# Power_LED_1.net
KiCad netlist of a schematic drawn in Altium Designer
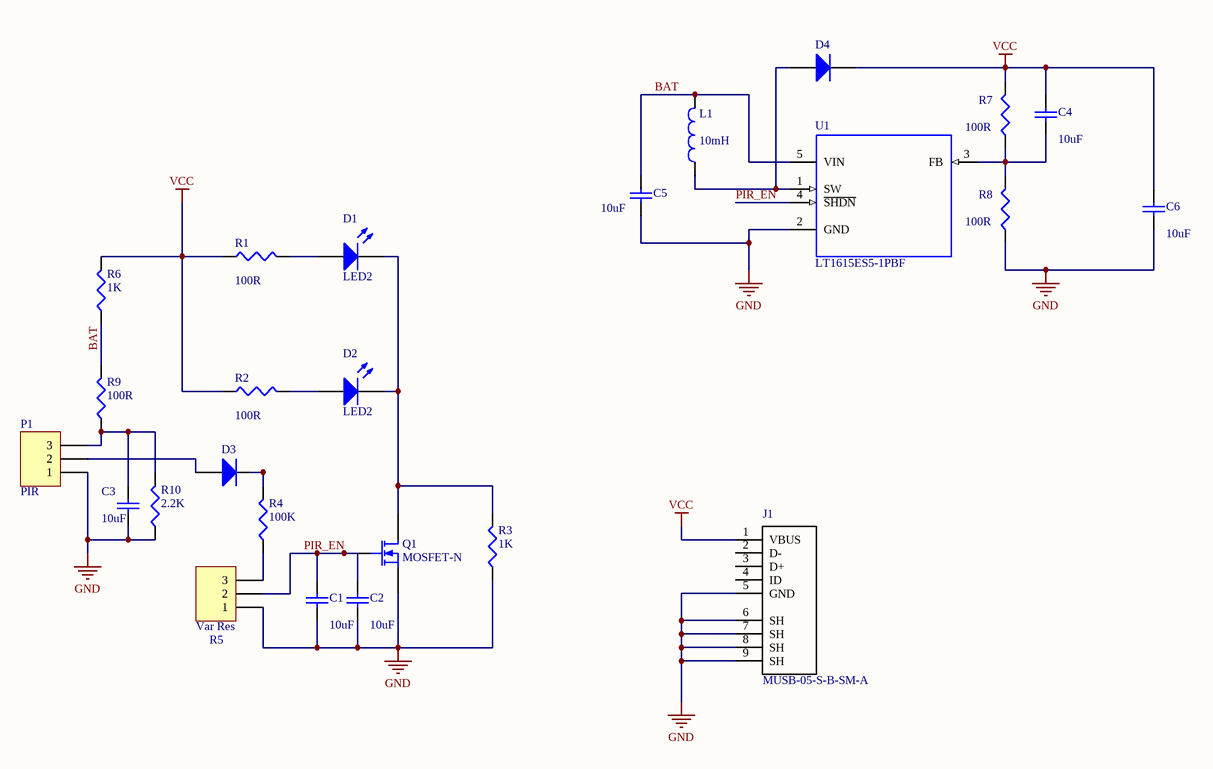
[diagram p0: Power_LED_1.SchDoc]

(export (version "E")
  (design (tool "Eeschema 10.0.6"))
  (components
    (comp (ref "C1")
      (value "10uF")
      (footprint "C1206")
      (description "Capacitor (Semiconductor SIM Model)")
      (fields (field (name "PUBLISHER") "Altium Limited"))
      (libsource (lib "Miscellaneous Devices") (part "Cap Semi"))
    )
    (comp (ref "C2")
      (value "10uF")
      (footprint "C0805")
      (description "Capacitor (Semiconductor SIM Model)")
      (fields (field (name "PUBLISHER") "Altium Limited"))
      (libsource (lib "Miscellaneous Devices") (part "Cap Semi"))
    )
    (comp (ref "C3")
      (value "10uF")
      (footprint "C1206")
      (description "Capacitor (Semiconductor SIM Model)")
      (fields (field (name "PUBLISHER") "Altium Limited"))
      (libsource (lib "Miscellaneous Devices") (part "Cap Semi"))
    )
    (comp (ref "C4")
      (value "10uF")
      (footprint "C0805")
      (description "Capacitor (Semiconductor SIM Model)")
      (fields (field (name "PUBLISHER") "Altium Limited"))
      (libsource (lib "Miscellaneous Devices") (part "Cap Semi"))
    )
    (comp (ref "C5")
      (value "10uF")
      (footprint "C0805")
      (description "Capacitor (Semiconductor SIM Model)")
      (fields (field (name "PUBLISHER") "Altium Limited"))
      (libsource (lib "Miscellaneous Devices") (part "Cap Semi"))
    )
    (comp (ref "C6")
      (value "10uF")
      (footprint "C0805")
      (description "Capacitor (Semiconductor SIM Model)")
      (fields (field (name "PUBLISHER") "Altium Limited"))
      (libsource (lib "Miscellaneous Devices") (part "Cap Semi"))
    )
    (comp (ref "D1")
      (value "LED2")
      (footprint "3.2X1.6X1.1")
      (description "Typical RED, GREEN, YELLOW, AMBER GaAs LED")
      (fields (field (name "PUBLISHER") "Altium Limited"))
      (libsource (lib "Miscellaneous Devices") (part "LED2"))
    )
    (comp (ref "D2")
      (value "LED2")
      (footprint "3.2X1.6X1.1")
      (description "Typical RED, GREEN, YELLOW, AMBER GaAs LED")
      (fields (field (name "PUBLISHER") "Altium Limited"))
      (libsource (lib "Miscellaneous Devices") (part "LED2"))
    )
    (comp (ref "D3")
      (value "~")
      (footprint "6-0805_L")
      (description "1 Amp General Purpose Rectifier")
      (fields (field (name "PUBLISHER") "Altium Limited"))
      (libsource (lib "Miscellaneous Devices") (part "Diode 1N4001"))
    )
    (comp (ref "D4")
      (value "~")
      (footprint "6-0805_L")
      (description "1 Amp General Purpose Rectifier")
      (fields (field (name "PUBLISHER") "Altium Limited"))
      (libsource (lib "Miscellaneous Devices") (part "Diode 1N4001"))
    )
    (comp (ref "J1")
      (value "MUSB-05-S-B-SM-A")
      (footprint "*SAMTEC_MUSB-05-S-B-SM-A")
      (description "Usb Interface 5-Contacts Surfacemount For Mini Usb Gold Mating Tin On Tails")
      (fields (field (name "MF") "Samtec") (field (name "DIGI-KEY_PART_NUMBER") "SAM8841-ND"))
      (libsource (lib "MUSB-05-S-B-SM-A") (part "MUSB-05-S-B-SM-A"))
    )
    (comp (ref "L1")
      (value "10mH")
      (footprint "6-0805_L")
      (description "Inductor")
      (fields (field (name "PUBLISHER") "Altium Limited"))
      (libsource (lib "Miscellaneous Devices") (part "Inductor"))
    )
    (comp (ref "P1")
      (value "PIR")
      (footprint "HDR1X3")
      (description "Header, 3-Pin")
      (fields (field (name "PUBLISHER") "Altium Limited"))
      (libsource (lib "Miscellaneous Connectors") (part "Header 3"))
    )
    (comp (ref "Q1")
      (value "MOSFET-N")
      (footprint "TO-220-AB")
      (description "N-Channel MOSFET")
      (fields (field (name "PUBLISHER") "Altium Limited"))
      (libsource (lib "Miscellaneous Devices") (part "MOSFET-N"))
    )
    (comp (ref "R1")
      (value "100R")
      (footprint "6-0805_L")
      (description "Resistor")
      (fields (field (name "PUBLISHER") "Altium Limited"))
      (libsource (lib "Miscellaneous Devices") (part "Res3"))
    )
    (comp (ref "R2")
      (value "100R")
      (footprint "6-0805_L")
      (description "Resistor")
      (fields (field (name "PUBLISHER") "Altium Limited"))
      (libsource (lib "Miscellaneous Devices") (part "Res3"))
    )
    (comp (ref "R3")
      (value "1K")
      (footprint "6-0805_L")
      (description "Resistor")
      (fields (field (name "PUBLISHER") "Altium Limited"))
      (libsource (lib "Miscellaneous Devices") (part "Res3"))
    )
    (comp (ref "R4")
      (value "100K")
      (footprint "6-0805_L")
      (description "Resistor")
      (fields (field (name "PUBLISHER") "Altium Limited"))
      (libsource (lib "Miscellaneous Devices") (part "Res3"))
    )
    (comp (ref "R5")
      (value "Var Res")
      (footprint "HDR1X3")
      (description "Header, 3-Pin")
      (fields (field (name "PUBLISHER") "Altium Limited"))
      (libsource (lib "Miscellaneous Connectors") (part "Header 3"))
    )
    (comp (ref "R6")
      (value "1K")
      (footprint "6-0805_L")
      (description "Resistor")
      (fields (field (name "PUBLISHER") "Altium Limited"))
      (libsource (lib "Miscellaneous Devices") (part "Res3"))
    )
    (comp (ref "R7")
      (value "100R")
      (footprint "6-0805_L")
      (description "Resistor")
      (fields (field (name "PUBLISHER") "Altium Limited"))
      (libsource (lib "Miscellaneous Devices") (part "Res3"))
    )
    (comp (ref "R8")
      (value "100R")
      (footprint "6-0805_L")
      (description "Resistor")
      (fields (field (name "PUBLISHER") "Altium Limited"))
      (libsource (lib "Miscellaneous Devices") (part "Res3"))
    )
    (comp (ref "R9")
      (value "100R")
      (footprint "6-0805_L")
      (description "Resistor")
      (fields (field (name "PUBLISHER") "Altium Limited"))
      (libsource (lib "Miscellaneous Devices") (part "Res3"))
    )
    (comp (ref "R10")
      (value "2.2K")
      (footprint "6-0805_L")
      (description "Resistor")
      (fields (field (name "PUBLISHER") "Altium Limited"))
      (libsource (lib "Miscellaneous Devices") (part "Res3"))
    )
    (comp (ref "U1")
      (value "LT1615ES5-1PBF")
      (footprint "LT1615ES5-1#PBF:SOT95P280X145-5N")
      (description "Micropower Step-Up DC/DC Converters")
      (fields (field (name "MF") "{'manufacturer': u'Analog Devices, Inc.'}"))
      (libsource (lib "*") (part "LT1615ES5-1PBF"))
    )
  )
  (nets
    (net (code "1") (name "/BAT") (class "Default")
      (node (ref "C5") (pin "2") (pinfunction "2_2") (pintype "passive"))
      (node (ref "L1") (pin "2") (pinfunction "2_2") (pintype "passive"))
      (node (ref "R6") (pin "1") (pinfunction "1_1") (pintype "passive"))
      (node (ref "R9") (pin "2") (pinfunction "2_2") (pintype "passive"))
      (node (ref "U1") (pin "5") (pinfunction "VIN_5") (pintype "power_in"))
    )
    (net (code "2") (name "/PIR_EN") (class "Default")
      (node (ref "C1") (pin "2") (pinfunction "2_2") (pintype "passive"))
      (node (ref "C2") (pin "2") (pinfunction "2_2") (pintype "passive"))
      (node (ref "Q1") (pin "2") (pinfunction "G_2") (pintype "passive"))
      (node (ref "R5") (pin "2") (pinfunction "2_2") (pintype "passive"))
      (node (ref "U1") (pin "4") (pinfunction "~{SHDN}_4") (pintype "input"))
    )
    (net (code "3") (name "GND") (class "Default")
      (node (ref "C1") (pin "1") (pinfunction "1_1") (pintype "passive"))
      (node (ref "C2") (pin "1") (pinfunction "1_1") (pintype "passive"))
      (node (ref "C3") (pin "1") (pinfunction "1_1") (pintype "passive"))
      (node (ref "C5") (pin "1") (pinfunction "1_1") (pintype "passive"))
      (node (ref "C6") (pin "1") (pinfunction "1_1") (pintype "passive"))
      (node (ref "J1") (pin "5") (pinfunction "GND_5") (pintype "passive"))
      (node (ref "J1") (pin "6") (pinfunction "SH_6") (pintype "passive"))
      (node (ref "J1") (pin "7") (pinfunction "SH_7") (pintype "passive"))
      (node (ref "J1") (pin "8") (pinfunction "SH_8") (pintype "passive"))
      (node (ref "J1") (pin "9") (pinfunction "SH_9") (pintype "passive"))
      (node (ref "P1") (pin "1") (pinfunction "1_1") (pintype "passive"))
      (node (ref "Q1") (pin "3") (pinfunction "S_3") (pintype "passive"))
      (node (ref "R10") (pin "1") (pinfunction "1_1") (pintype "passive"))
      (node (ref "R3") (pin "1") (pinfunction "1_1") (pintype "passive"))
      (node (ref "R5") (pin "1") (pinfunction "1_1") (pintype "passive"))
      (node (ref "R8") (pin "1") (pinfunction "1_1") (pintype "passive"))
      (node (ref "U1") (pin "2") (pinfunction "GND_2") (pintype "passive"))
    )
    (net (code "4") (name "Net-(C3-Pad2)") (class "Default")
      (node (ref "C3") (pin "2") (pinfunction "2_2") (pintype "passive"))
      (node (ref "P1") (pin "3") (pinfunction "3_3") (pintype "passive"))
      (node (ref "R10") (pin "2") (pinfunction "2_2") (pintype "passive"))
      (node (ref "R9") (pin "1") (pinfunction "1_1") (pintype "passive"))
    )
    (net (code "5") (name "Net-(D1-A)") (class "Default")
      (node (ref "D1") (pin "1") (pinfunction "A_1") (pintype "passive"))
      (node (ref "R1") (pin "2") (pinfunction "2_2") (pintype "passive"))
    )
    (net (code "6") (name "Net-(D1-K)") (class "Default")
      (node (ref "D1") (pin "2") (pinfunction "K_2") (pintype "passive"))
      (node (ref "D2") (pin "2") (pinfunction "K_2") (pintype "passive"))
      (node (ref "Q1") (pin "1") (pinfunction "D_1") (pintype "passive"))
      (node (ref "R3") (pin "2") (pinfunction "2_2") (pintype "passive"))
    )
    (net (code "7") (name "Net-(D2-A)") (class "Default")
      (node (ref "D2") (pin "1") (pinfunction "A_1") (pintype "passive"))
      (node (ref "R2") (pin "2") (pinfunction "2_2") (pintype "passive"))
    )
    (net (code "8") (name "Net-(D3-A)") (class "Default")
      (node (ref "D3") (pin "1") (pinfunction "A_1") (pintype "passive"))
      (node (ref "P1") (pin "2") (pinfunction "2_2") (pintype "passive"))
    )
    (net (code "9") (name "Net-(D3-K)") (class "Default")
      (node (ref "D3") (pin "2") (pinfunction "K_2") (pintype "passive"))
      (node (ref "R4") (pin "2") (pinfunction "2_2") (pintype "passive"))
    )
    (net (code "10") (name "Net-(D4-A)") (class "Default")
      (node (ref "D4") (pin "1") (pinfunction "A_1") (pintype "passive"))
      (node (ref "L1") (pin "1") (pinfunction "1_1") (pintype "passive"))
      (node (ref "U1") (pin "1") (pinfunction "SW_1") (pintype "input"))
    )
    (net (code "11") (name "Net-(R4-Pad1)") (class "Default")
      (node (ref "R4") (pin "1") (pinfunction "1_1") (pintype "passive"))
      (node (ref "R5") (pin "3") (pinfunction "3_3") (pintype "passive"))
    )
    (net (code "12") (name "Net-(U1-FB)") (class "Default")
      (node (ref "C4") (pin "1") (pinfunction "1_1") (pintype "passive"))
      (node (ref "R7") (pin "1") (pinfunction "1_1") (pintype "passive"))
      (node (ref "R8") (pin "2") (pinfunction "2_2") (pintype "passive"))
      (node (ref "U1") (pin "3") (pinfunction "FB_3") (pintype "input"))
    )
    (net (code "13") (name "VCC") (class "Default")
      (node (ref "C4") (pin "2") (pinfunction "2_2") (pintype "passive"))
      (node (ref "C6") (pin "2") (pinfunction "2_2") (pintype "passive"))
      (node (ref "D4") (pin "2") (pinfunction "K_2") (pintype "passive"))
      (node (ref "J1") (pin "1") (pinfunction "VBUS_1") (pintype "passive"))
      (node (ref "R1") (pin "1") (pinfunction "1_1") (pintype "passive"))
      (node (ref "R2") (pin "1") (pinfunction "1_1") (pintype "passive"))
      (node (ref "R6") (pin "2") (pinfunction "2_2") (pintype "passive"))
      (node (ref "R7") (pin "2") (pinfunction "2_2") (pintype "passive"))
    )
    (net (code "14") (name "unconnected-(J1-D+-Pad3)") (class "Default")
      (node (ref "J1") (pin "3") (pinfunction "D+_3") (pintype "passive"))
    )
    (net (code "15") (name "unconnected-(J1-D--Pad2)") (class "Default")
      (node (ref "J1") (pin "2") (pinfunction "D-_2") (pintype "passive"))
    )
    (net (code "16") (name "unconnected-(J1-ID-Pad4)") (class "Default")
      (node (ref "J1") (pin "4") (pinfunction "ID_4") (pintype "passive"))
    )
  )
)
